# BRMDOOR_control_board.net
KiCad netlist of a schematic drawn in EAGLE
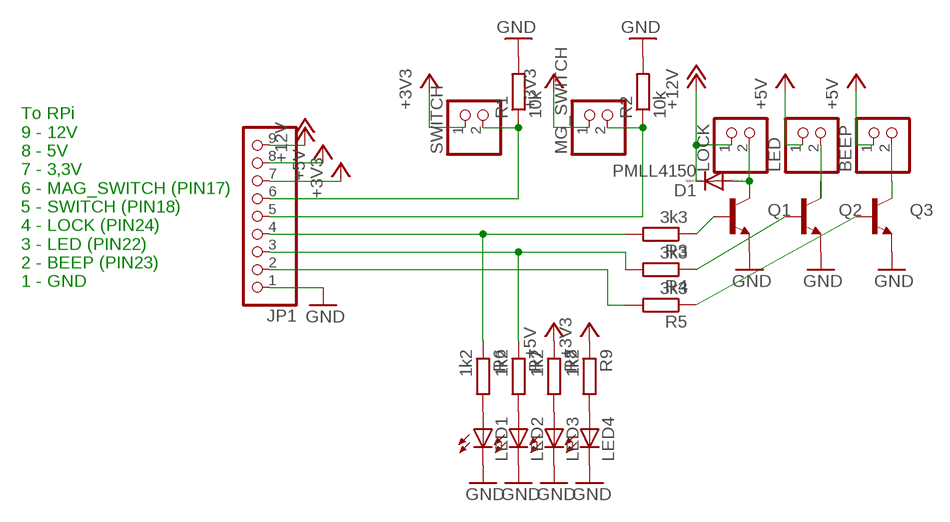
[diagram p0: schematic, sheet 1]

(export (version "E")
  (design (tool "Eeschema 10.0.6"))
  (components
    (comp (ref "BEEP")
      (value "PINHD-1X2")
      (footprint "eagle-import:1X02")
      (libsource (lib "eagle-import") (part "PINHD-1X2"))
    )
    (comp (ref "D1")
      (value "PMLL4150")
      (footprint "eagle-import:SOD80C")
      (libsource (lib "eagle-import") (part "PMLL4150"))
    )
    (comp (ref "JP1")
      (value "PINHD-1X9")
      (footprint "eagle-import:1X09")
      (libsource (lib "eagle-import") (part "PINHD-1X9"))
    )
    (comp (ref "LED")
      (value "PINHD-1X2")
      (footprint "eagle-import:1X02")
      (libsource (lib "eagle-import") (part "PINHD-1X2"))
    )
    (comp (ref "LED1")
      (value "LEDKA-3528ASYC")
      (footprint "eagle-import:KA-3528ASYC")
      (libsource (lib "eagle-import") (part "LEDKA-3528ASYC"))
    )
    (comp (ref "LED2")
      (value "LEDKA-3528ASYC")
      (footprint "eagle-import:KA-3528ASYC")
      (libsource (lib "eagle-import") (part "LEDKA-3528ASYC"))
    )
    (comp (ref "LED3")
      (value "LEDKA-3528ASYC")
      (footprint "eagle-import:KA-3528ASYC")
      (libsource (lib "eagle-import") (part "LEDKA-3528ASYC"))
    )
    (comp (ref "LED4")
      (value "LEDKA-3528ASYC")
      (footprint "eagle-import:KA-3528ASYC")
      (libsource (lib "eagle-import") (part "LEDKA-3528ASYC"))
    )
    (comp (ref "LOCK")
      (value "PINHD-1X2")
      (footprint "eagle-import:1X02")
      (libsource (lib "eagle-import") (part "PINHD-1X2"))
    )
    (comp (ref "MG_SWITCH")
      (value "PINHD-1X2")
      (footprint "eagle-import:1X02")
      (libsource (lib "eagle-import") (part "PINHD-1X2"))
    )
    (comp (ref "Q1")
      (value "TRANSISTOR_NPNSMD2")
      (footprint "eagle-import:SOT223")
      (libsource (lib "eagle-import") (part "TRANSISTOR_NPNSMD2"))
    )
    (comp (ref "Q2")
      (value "TRANSISTOR_NPNSMD2")
      (footprint "eagle-import:SOT223")
      (libsource (lib "eagle-import") (part "TRANSISTOR_NPNSMD2"))
    )
    (comp (ref "Q3")
      (value "TRANSISTOR_NPNSMD2")
      (footprint "eagle-import:SOT223")
      (libsource (lib "eagle-import") (part "TRANSISTOR_NPNSMD2"))
    )
    (comp (ref "R1")
      (value "10k")
      (footprint "eagle-import:M1206")
      (libsource (lib "eagle-import") (part "R-EU_M1206"))
    )
    (comp (ref "R2")
      (value "10k")
      (footprint "eagle-import:M1206")
      (libsource (lib "eagle-import") (part "R-EU_M1206"))
    )
    (comp (ref "R3")
      (value "3k3")
      (footprint "eagle-import:M1206")
      (libsource (lib "eagle-import") (part "R-EU_M1206"))
    )
    (comp (ref "R4")
      (value "3k3")
      (footprint "eagle-import:M1206")
      (libsource (lib "eagle-import") (part "R-EU_M1206"))
    )
    (comp (ref "R5")
      (value "3k3")
      (footprint "eagle-import:M1206")
      (libsource (lib "eagle-import") (part "R-EU_M1206"))
    )
    (comp (ref "R6")
      (value "1k2")
      (footprint "eagle-import:M1206")
      (libsource (lib "eagle-import") (part "R-EU_M1206"))
    )
    (comp (ref "R7")
      (value "1k2")
      (footprint "eagle-import:M1206")
      (libsource (lib "eagle-import") (part "R-EU_M1206"))
    )
    (comp (ref "R8")
      (value "1k2")
      (footprint "eagle-import:M1206")
      (libsource (lib "eagle-import") (part "R-EU_M1206"))
    )
    (comp (ref "R9")
      (value "1k2")
      (footprint "eagle-import:M1206")
      (libsource (lib "eagle-import") (part "R-EU_M1206"))
    )
    (comp (ref "SWITCH")
      (value "PINHD-1X2")
      (footprint "eagle-import:1X02")
      (libsource (lib "eagle-import") (part "PINHD-1X2"))
    )
  )
  (nets
    (net (code "1") (name "+3V3") (class "Default")
      (node (ref "JP1") (pin "7") (pinfunction "7_7") (pintype "passive"))
      (node (ref "MG_SWITCH") (pin "1") (pinfunction "1_1") (pintype "passive"))
      (node (ref "R9") (pin "1") (pinfunction "1_1") (pintype "passive"))
      (node (ref "SWITCH") (pin "1") (pinfunction "1_1") (pintype "passive"))
    )
    (net (code "2") (name "+5V") (class "Default")
      (node (ref "BEEP") (pin "1") (pinfunction "1_1") (pintype "passive"))
      (node (ref "JP1") (pin "8") (pinfunction "8_8") (pintype "passive"))
      (node (ref "LED") (pin "1") (pinfunction "1_1") (pintype "passive"))
      (node (ref "R8") (pin "1") (pinfunction "1_1") (pintype "passive"))
    )
    (net (code "3") (name "+12V") (class "Default")
      (node (ref "D1") (pin "C") (pinfunction "C_C") (pintype "passive"))
      (node (ref "JP1") (pin "9") (pinfunction "9_9") (pintype "passive"))
      (node (ref "LOCK") (pin "1") (pinfunction "1_1") (pintype "passive"))
    )
    (net (code "4") (name "GND") (class "Default")
      (node (ref "JP1") (pin "1") (pinfunction "1_1") (pintype "passive"))
      (node (ref "LED1") (pin "C") (pinfunction "C_C") (pintype "passive"))
      (node (ref "LED2") (pin "C") (pinfunction "C_C") (pintype "passive"))
      (node (ref "LED3") (pin "C") (pinfunction "C_C") (pintype "passive"))
      (node (ref "LED4") (pin "C") (pinfunction "C_C") (pintype "passive"))
      (node (ref "Q1") (pin "3") (pinfunction "E_3") (pintype "passive"))
      (node (ref "Q2") (pin "3") (pinfunction "E_3") (pintype "passive"))
      (node (ref "Q3") (pin "3") (pinfunction "E_3") (pintype "passive"))
      (node (ref "R1") (pin "2") (pinfunction "2_2") (pintype "passive"))
      (node (ref "R2") (pin "2") (pinfunction "2_2") (pintype "passive"))
    )
    (net (code "5") (name "Net-(JP1-Pad2)") (class "Default")
      (node (ref "JP1") (pin "2") (pinfunction "2_2") (pintype "passive"))
      (node (ref "R5") (pin "2") (pinfunction "2_2") (pintype "passive"))
    )
    (net (code "6") (name "Net-(JP1-Pad3)") (class "Default")
      (node (ref "JP1") (pin "3") (pinfunction "3_3") (pintype "passive"))
      (node (ref "R4") (pin "2") (pinfunction "2_2") (pintype "passive"))
      (node (ref "R7") (pin "1") (pinfunction "1_1") (pintype "passive"))
    )
    (net (code "7") (name "Net-(JP1-Pad4)") (class "Default")
      (node (ref "JP1") (pin "4") (pinfunction "4_4") (pintype "passive"))
      (node (ref "R3") (pin "2") (pinfunction "2_2") (pintype "passive"))
      (node (ref "R6") (pin "1") (pinfunction "1_1") (pintype "passive"))
    )
    (net (code "8") (name "Net-(JP1-Pad5)") (class "Default")
      (node (ref "JP1") (pin "5") (pinfunction "5_5") (pintype "passive"))
      (node (ref "MG_SWITCH") (pin "2") (pinfunction "2_2") (pintype "passive"))
      (node (ref "R2") (pin "1") (pinfunction "1_1") (pintype "passive"))
    )
    (net (code "9") (name "Net-(JP1-Pad6)") (class "Default")
      (node (ref "JP1") (pin "6") (pinfunction "6_6") (pintype "passive"))
      (node (ref "R1") (pin "1") (pinfunction "1_1") (pintype "passive"))
      (node (ref "SWITCH") (pin "2") (pinfunction "2_2") (pintype "passive"))
    )
    (net (code "10") (name "Net-(LED1-PadA)") (class "Default")
      (node (ref "LED1") (pin "A") (pinfunction "A_A") (pintype "passive"))
      (node (ref "R6") (pin "2") (pinfunction "2_2") (pintype "passive"))
    )
    (net (code "11") (name "Net-(LED2-PadA)") (class "Default")
      (node (ref "LED2") (pin "A") (pinfunction "A_A") (pintype "passive"))
      (node (ref "R7") (pin "2") (pinfunction "2_2") (pintype "passive"))
    )
    (net (code "12") (name "Net-(LED3-PadA)") (class "Default")
      (node (ref "LED3") (pin "A") (pinfunction "A_A") (pintype "passive"))
      (node (ref "R8") (pin "2") (pinfunction "2_2") (pintype "passive"))
    )
    (net (code "13") (name "Net-(LED4-PadA)") (class "Default")
      (node (ref "LED4") (pin "A") (pinfunction "A_A") (pintype "passive"))
      (node (ref "R9") (pin "2") (pinfunction "2_2") (pintype "passive"))
    )
    (net (code "14") (name "Net-(Q1-B)") (class "Default")
      (node (ref "Q1") (pin "1") (pinfunction "B_1") (pintype "passive"))
      (node (ref "R3") (pin "1") (pinfunction "1_1") (pintype "passive"))
    )
    (net (code "15") (name "Net-(Q1-C)") (class "Default")
      (node (ref "D1") (pin "A") (pinfunction "A_A") (pintype "passive"))
      (node (ref "LOCK") (pin "2") (pinfunction "2_2") (pintype "passive"))
      (node (ref "Q1") (pin "2") (pinfunction "C_2") (pintype "passive"))
    )
    (net (code "16") (name "Net-(Q2-B)") (class "Default")
      (node (ref "Q2") (pin "1") (pinfunction "B_1") (pintype "passive"))
      (node (ref "R4") (pin "1") (pinfunction "1_1") (pintype "passive"))
    )
    (net (code "17") (name "Net-(Q2-C)") (class "Default")
      (node (ref "LED") (pin "2") (pinfunction "2_2") (pintype "passive"))
      (node (ref "Q2") (pin "2") (pinfunction "C_2") (pintype "passive"))
    )
    (net (code "18") (name "Net-(Q3-B)") (class "Default")
      (node (ref "Q3") (pin "1") (pinfunction "B_1") (pintype "passive"))
      (node (ref "R5") (pin "1") (pinfunction "1_1") (pintype "passive"))
    )
    (net (code "19") (name "Net-(Q3-C)") (class "Default")
      (node (ref "BEEP") (pin "2") (pinfunction "2_2") (pintype "passive"))
      (node (ref "Q3") (pin "2") (pinfunction "C_2") (pintype "passive"))
    )
  )
)
